# ESP32.net
KiCad netlist of a schematic drawn in Altium Designer
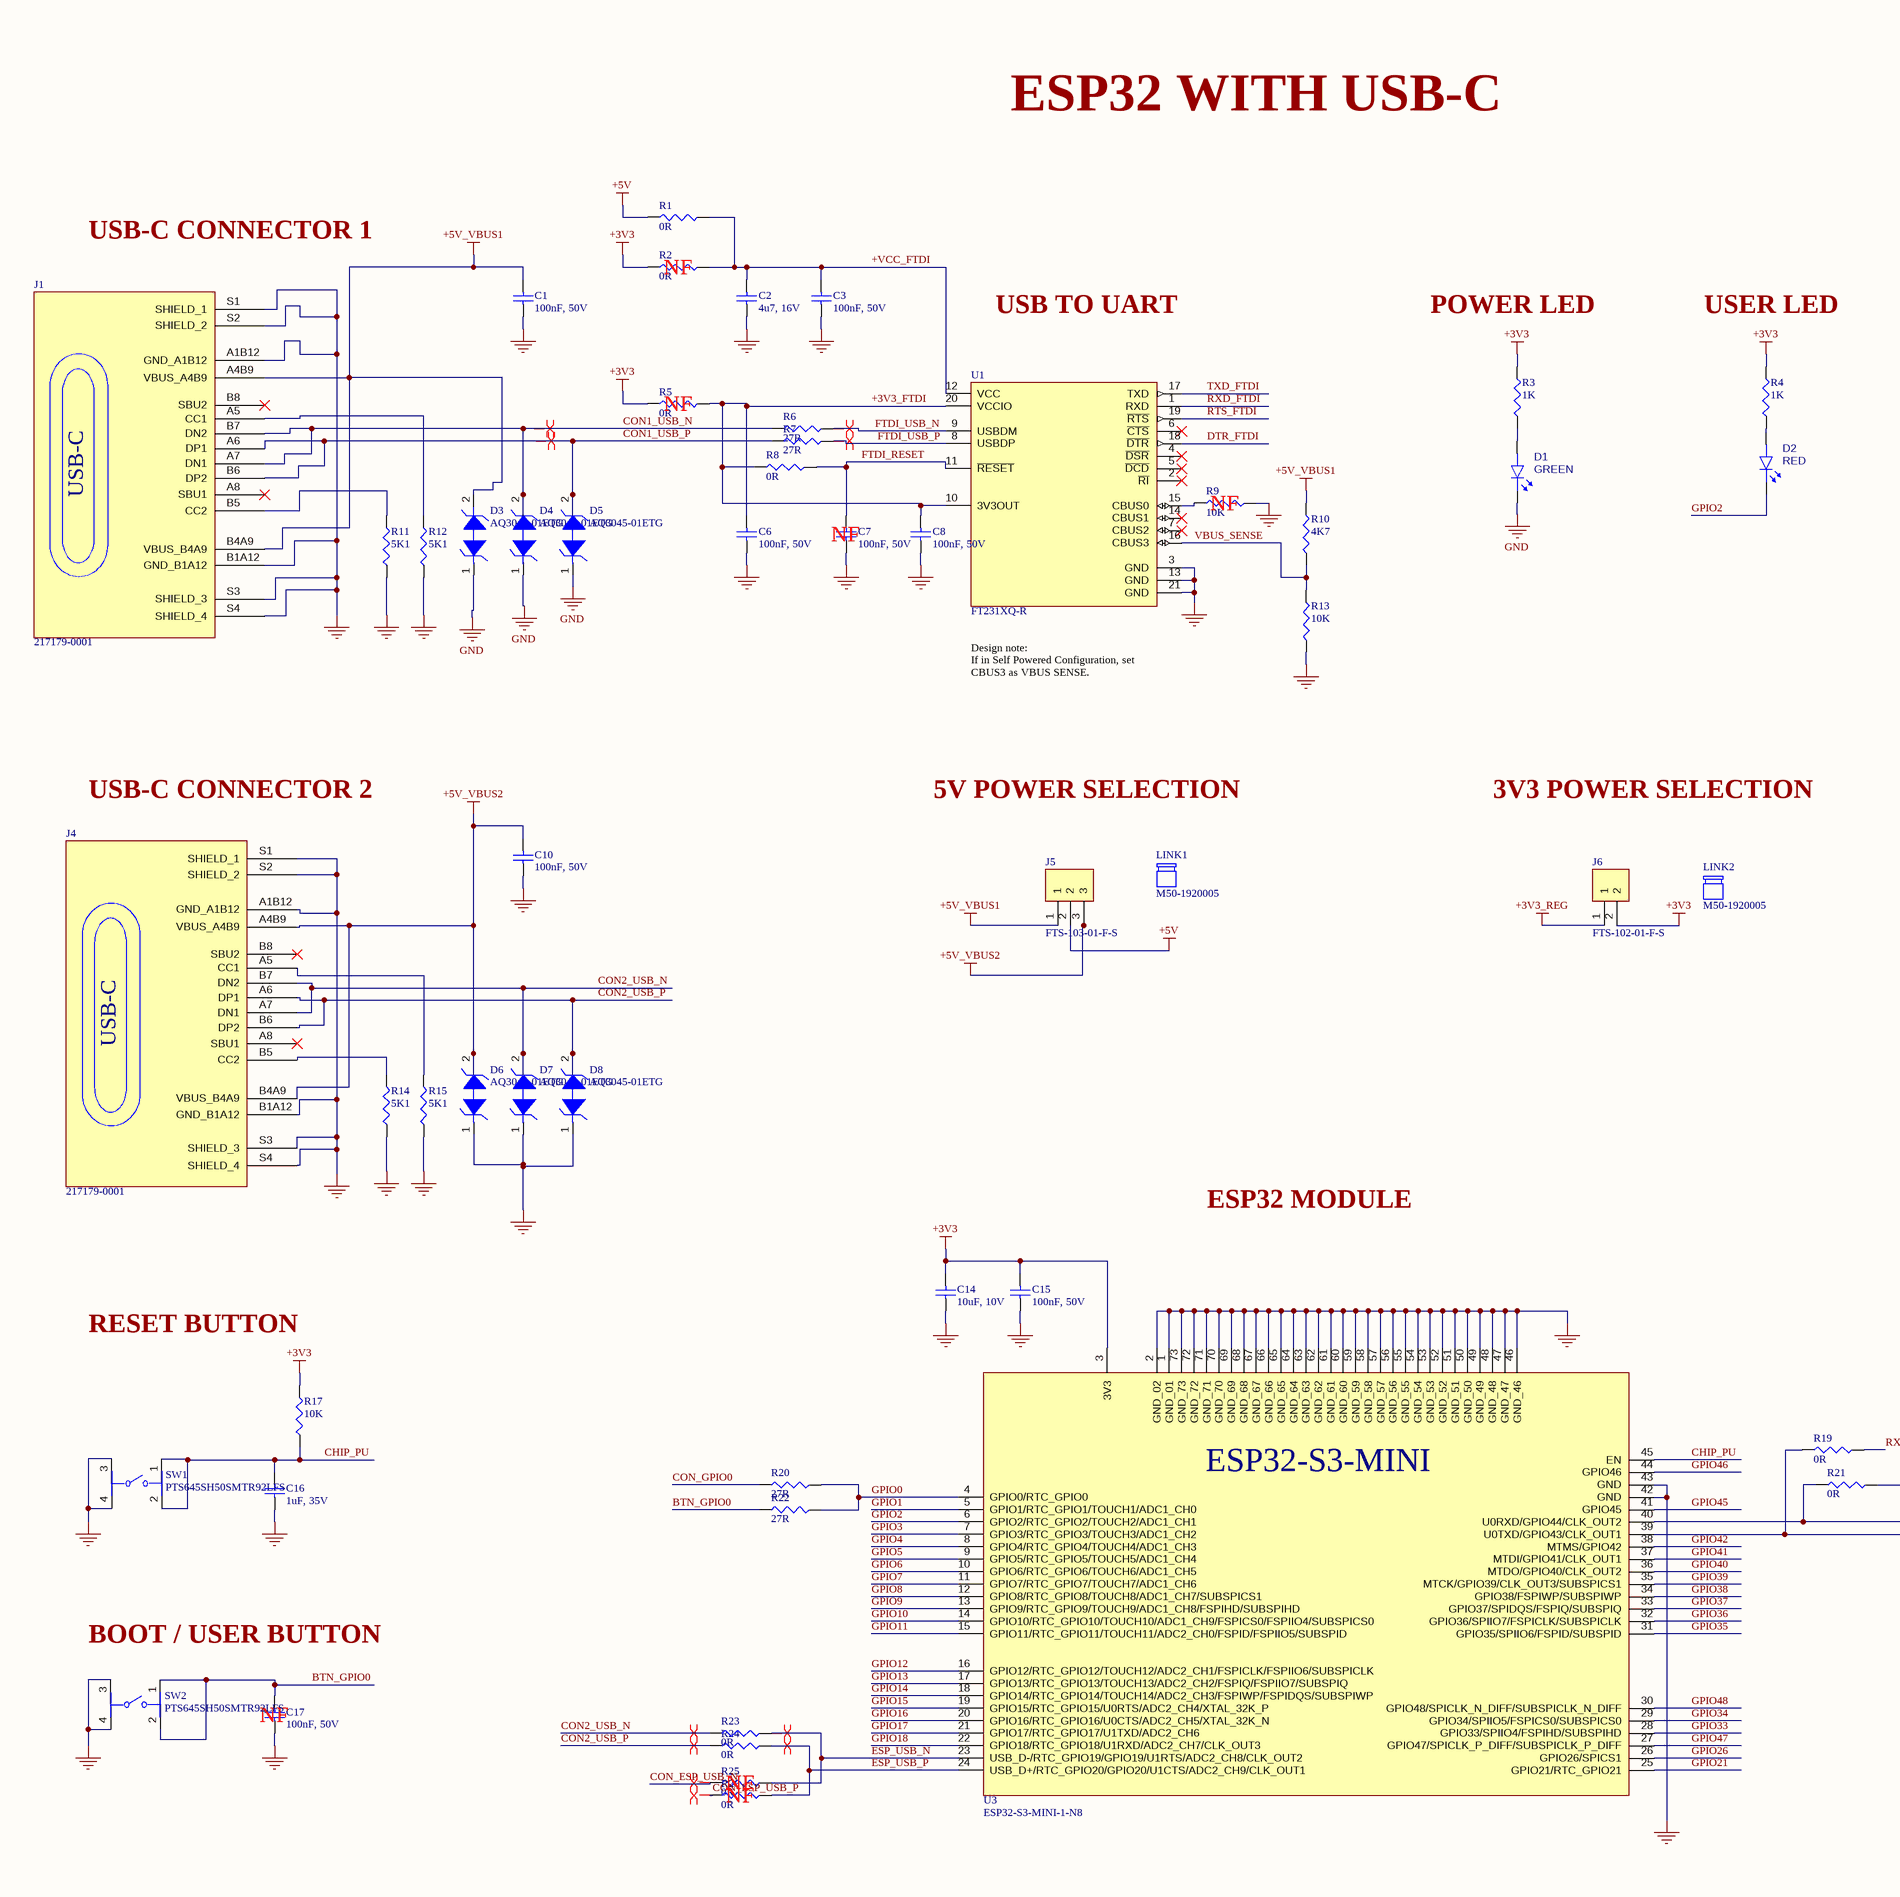
[diagram p0: ESP32.SchDoc, left]
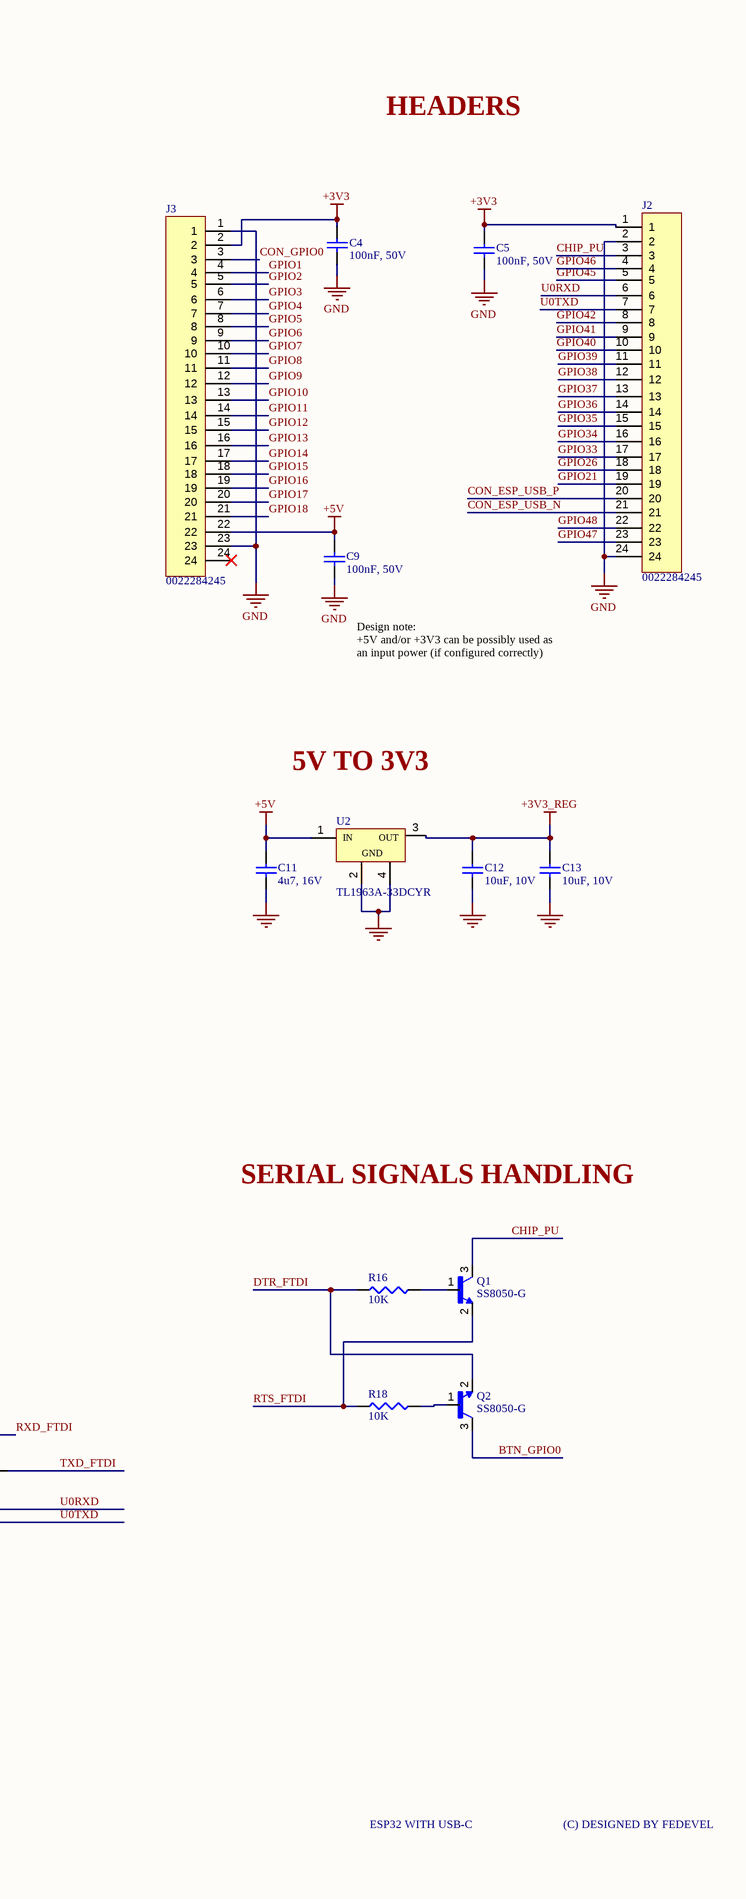
[diagram p1: ESP32.SchDoc, right]

(export (version "E")
  (design (tool "Eeschema 10.0.6"))
  (components
    (comp (ref "C1")
      (value "100nF, 50V")
      (footprint "CAPC1005X55N")
      (description "CAP CER 0.1UF 50V X7R 0402")
      (fields
        (field (name "MANUFACTURER") "Samsung")
        (field (name "MANUFACTURER PART NUMBER") "CL05B104KB54PNC")
      )
      (libsource (lib "ESP32") (part "CL05B104KB54PNC"))
    )
    (comp (ref "C2")
      (value "4u7, 16V")
      (footprint "CAPC1005X55N")
      (description "CAP CER 4.7UF 16V X5R 0402")
      (fields
        (field (name "MANUFACTURER") "Samsung")
        (field (name "MANUFACTURER PART NUMBER") "CL05A475MO5NUNC")
      )
      (libsource (lib "ESP32") (part "CL05A475MO5NUNC"))
    )
    (comp (ref "C3")
      (value "100nF, 50V")
      (footprint "CAPC1005X55N")
      (description "CAP CER 0.1UF 50V X7R 0402")
      (fields
        (field (name "MANUFACTURER") "Samsung")
        (field (name "MANUFACTURER PART NUMBER") "CL05B104KB54PNC")
      )
      (libsource (lib "ESP32") (part "CL05B104KB54PNC"))
    )
    (comp (ref "C4")
      (value "100nF, 50V")
      (footprint "CAPC1005X55N")
      (description "CAP CER 0.1UF 50V X7R 0402")
      (fields
        (field (name "MANUFACTURER") "Samsung")
        (field (name "MANUFACTURER PART NUMBER") "CL05B104KB54PNC")
      )
      (libsource (lib "Schlib") (part "CL05B104KB54PNC"))
    )
    (comp (ref "C5")
      (value "100nF, 50V")
      (footprint "CAPC1005X55N")
      (description "CAP CER 0.1UF 50V X7R 0402")
      (fields
        (field (name "MANUFACTURER") "Samsung")
        (field (name "MANUFACTURER PART NUMBER") "CL05B104KB54PNC")
      )
      (libsource (lib "Schlib") (part "CL05B104KB54PNC"))
    )
    (comp (ref "C6")
      (value "100nF, 50V")
      (footprint "CAPC1005X55N")
      (description "CAP CER 0.1UF 50V X7R 0402")
      (fields
        (field (name "MANUFACTURER") "Samsung")
        (field (name "MANUFACTURER PART NUMBER") "CL05B104KB54PNC")
      )
      (libsource (lib "Schlib") (part "CL05B104KB54PNC"))
    )
    (comp (ref "C7")
      (value "100nF, 50V")
      (footprint "CAPC1005X55N")
      (description "CAP CER 0.1UF 50V X7R 0402")
      (fields
        (field (name "MANUFACTURER") "Samsung")
        (field (name "MANUFACTURER PART NUMBER") "CL05B104KB54PNC")
      )
      (libsource (lib "Schlib") (part "CL05B104KB54PNC"))
    )
    (comp (ref "C8")
      (value "100nF, 50V")
      (footprint "CAPC1005X55N")
      (description "CAP CER 0.1UF 50V X7R 0402")
      (fields
        (field (name "MANUFACTURER") "Samsung")
        (field (name "MANUFACTURER PART NUMBER") "CL05B104KB54PNC")
      )
      (libsource (lib "Schlib") (part "CL05B104KB54PNC"))
    )
    (comp (ref "C9")
      (value "100nF, 50V")
      (footprint "CAPC1005X55N")
      (description "CAP CER 0.1UF 50V X7R 0402")
      (fields
        (field (name "MANUFACTURER") "Samsung")
        (field (name "MANUFACTURER PART NUMBER") "CL05B104KB54PNC")
      )
      (libsource (lib "Schlib") (part "CL05B104KB54PNC"))
    )
    (comp (ref "C10")
      (value "100nF, 50V")
      (footprint "CAPC1005X55N")
      (description "CAP CER 0.1UF 50V X7R 0402")
      (fields
        (field (name "MANUFACTURER") "Samsung")
        (field (name "MANUFACTURER PART NUMBER") "CL05B104KB54PNC")
      )
      (libsource (lib "Schlib") (part "CL05B104KB54PNC"))
    )
    (comp (ref "C11")
      (value "4u7, 16V")
      (footprint "CAPC1005X55N")
      (description "CAP CER 4.7UF 16V X5R 0402")
      (fields
        (field (name "MANUFACTURER") "Samsung")
        (field (name "MANUFACTURER PART NUMBER") "CL05A475MO5NUNC")
      )
      (libsource (lib "Schlib") (part "CL05A475MO5NUNC"))
    )
    (comp (ref "C12")
      (value "10uF, 10V")
      (footprint "CAPC1005X55N")
      (description "CAP CER 10UF 10V X5R 0402")
      (fields
        (field (name "MANUFACTURER") "Samsung")
        (field (name "MANUFACTURER PART NUMBER") "CL05A106MP8NUB8")
      )
      (libsource (lib "ESP32") (part "CL05A106MP8NUB8"))
    )
    (comp (ref "C13")
      (value "10uF, 10V")
      (footprint "CAPC1005X55N")
      (description "CAP CER 10UF 10V X5R 0402")
      (fields
        (field (name "MANUFACTURER") "Samsung")
        (field (name "MANUFACTURER PART NUMBER") "CL05A106MP8NUB8")
      )
      (libsource (lib "Schlib") (part "CL05A106MP8NUB8"))
    )
    (comp (ref "C14")
      (value "10uF, 10V")
      (footprint "CAPC1005X55N")
      (description "CAP CER 10UF 10V X5R 0402")
      (fields
        (field (name "MANUFACTURER") "Samsung")
        (field (name "MANUFACTURER PART NUMBER") "CL05A106MP8NUB8")
      )
      (libsource (lib "ESP32") (part "CL05A106MP8NUB8"))
    )
    (comp (ref "C15")
      (value "100nF, 50V")
      (footprint "CAPC1005X55N")
      (description "CAP CER 0.1UF 50V X7R 0402")
      (fields
        (field (name "MANUFACTURER") "Samsung")
        (field (name "MANUFACTURER PART NUMBER") "CL05B104KB54PNC")
      )
      (libsource (lib "ESP32") (part "CL05B104KB54PNC"))
    )
    (comp (ref "C16")
      (value "1uF, 35V")
      (footprint "CAPC1005X55N")
      (description "CAP CER 1UF 35V X5R 0402")
      (fields
        (field (name "MANUFACTURER") "Samsung")
        (field (name "MANUFACTURER PART NUMBER") "CL05A105KL5NRNC")
      )
      (libsource (lib "Schlib") (part "CL05A105KL5NRNC"))
    )
    (comp (ref "C17")
      (value "100nF, 50V")
      (footprint "CAPC1005X55N")
      (description "CAP CER 0.1UF 50V X7R 0402")
      (fields
        (field (name "MANUFACTURER") "Samsung")
        (field (name "MANUFACTURER PART NUMBER") "CL05B104KB54PNC")
      )
      (libsource (lib "Schlib") (part "CL05B104KB54PNC"))
    )
    (comp (ref "D1")
      (value "GREEN")
      (footprint "QTB-QBLP595_V")
      (description "Chip LED 0402, Green, 0.02 A, 3.1 to 3.7 V, -40 to 80 degC, 2-Pin SMD, RoHS, Tape and Reel")
      (libsource (lib "KARTHICK RAJ R") (part "LED-KA-2"))
    )
    (comp (ref "D2")
      (value "RED")
      (footprint "QTB-QBLP595_V")
      (description "Chip LED 0402, Red, 0.02 A, 2.0 to 2.5 V, -40 to 80 degC, 2-Pin SMD, RoHS, Tape and Reel")
      (libsource (lib "KARTHICK RAJ R") (part "LED-KA-2"))
    )
    (comp (ref "D3")
      (value "AQ3045-01ETG")
      (footprint "AQ3045-01ETG")
      (description "Bi 30Kv 5V 0.35Pf Automotve Tvs Sod882/ T&r Rohs Compliant: Yes ¦Littelfuse AQ3045-01ETG")
      (fields (field (name "MANUFACTURER") "Littelfuse"))
      (libsource (lib "ESP32") (part "AQ3045-01ETG"))
    )
    (comp (ref "D4")
      (value "AQ3045-01ETG")
      (footprint "AQ3045-01ETG")
      (description "Bi 30Kv 5V 0.35Pf Automotve Tvs Sod882/ T&r Rohs Compliant: Yes ¦Littelfuse AQ3045-01ETG")
      (fields (field (name "MANUFACTURER") "Littelfuse"))
      (libsource (lib "ESP32") (part "AQ3045-01ETG"))
    )
    (comp (ref "D5")
      (value "AQ3045-01ETG")
      (footprint "AQ3045-01ETG")
      (description "Bi 30Kv 5V 0.35Pf Automotve Tvs Sod882/ T&r Rohs Compliant: Yes ¦Littelfuse AQ3045-01ETG")
      (fields (field (name "MANUFACTURER") "Littelfuse"))
      (libsource (lib "ESP32") (part "AQ3045-01ETG"))
    )
    (comp (ref "D6")
      (value "AQ3045-01ETG")
      (footprint "AQ3045-01ETG")
      (description "Bi 30Kv 5V 0.35Pf Automotve Tvs Sod882/ T&r Rohs Compliant: Yes ¦Littelfuse AQ3045-01ETG")
      (fields (field (name "MANUFACTURER") "Littelfuse"))
      (libsource (lib "ESP32") (part "AQ3045-01ETG"))
    )
    (comp (ref "D7")
      (value "AQ3045-01ETG")
      (footprint "AQ3045-01ETG")
      (description "Bi 30Kv 5V 0.35Pf Automotve Tvs Sod882/ T&r Rohs Compliant: Yes ¦Littelfuse AQ3045-01ETG")
      (fields (field (name "MANUFACTURER") "Littelfuse"))
      (libsource (lib "ESP32") (part "AQ3045-01ETG"))
    )
    (comp (ref "D8")
      (value "AQ3045-01ETG")
      (footprint "AQ3045-01ETG")
      (description "Bi 30Kv 5V 0.35Pf Automotve Tvs Sod882/ T&r Rohs Compliant: Yes ¦Littelfuse AQ3045-01ETG")
      (fields (field (name "MANUFACTURER") "Littelfuse"))
      (libsource (lib "ESP32") (part "AQ3045-01ETG"))
    )
    (comp (ref "J1")
      (value "217179-0001")
      (footprint "2171790001")
      (description "USB Connector, USB Type C, USB 2.0, Receptacle, 16 Ways, Surface Mount, Through Hole Mount")
      (fields (field (name "MANUFACTURER") "Molex"))
      (libsource (lib "ESP32") (part "217179-0001"))
    )
    (comp (ref "J2")
      (value "0022284245")
      (footprint "0022284245")
      (description "Conn Unshrouded Header HDR 24 POS 2.54mm Solder ST Thru-Hole KK® Bag")
      (fields (field (name "MANUFACTURER") "Molex") (field (name "MANUFACTURER PART NUMBER") "22-28-4245"))
      (libsource (lib "ESP32") (part "0022284245"))
    )
    (comp (ref "J3")
      (value "0022284245")
      (footprint "0022284245")
      (description "Conn Unshrouded Header HDR 24 POS 2.54mm Solder ST Thru-Hole KK® Bag")
      (fields (field (name "MANUFACTURER") "Molex") (field (name "MANUFACTURER PART NUMBER") "22-28-4245"))
      (libsource (lib "") (part "0022284245_1"))
    )
    (comp (ref "J4")
      (value "217179-0001")
      (footprint "2171790001")
      (description "USB Connector, USB Type C, USB 2.0, Receptacle, 16 Ways, Surface Mount, Through Hole Mount")
      (fields (field (name "MANUFACTURER") "Molex"))
      (libsource (lib "ESP32") (part "217179-0001"))
    )
    (comp (ref "J5")
      (value "FTS-103-01-F-S")
      (footprint "FTS-103-01-X-S")
      (description "Pin Header, Wire-to-Board, 1.27 mm, 1 Rows, 3 Contacts, Through Hole, FTS")
      (fields (field (name "MANUFACTURER") "Samtec") (field (name "LCSC PART NUMBER") "C3333578"))
      (libsource (lib "ESP32") (part "FTS-103-01-F-S"))
    )
    (comp (ref "J6")
      (value "FTS-102-01-F-S")
      (footprint "FTS-102-01-X-S")
      (description "Pin Header, Board-to-Board, 1.27 mm, 1 Rows, 2 Contacts, Through Hole Straight, FTS Series")
      (fields (field (name "MANUFACTURER") "Samtec"))
      (libsource (lib "ESP32") (part "FTS-102-01-F-S"))
    )
    (comp (ref "LINK1")
      (value "M50-1920005")
      (description "CONN SHUNT 1.27MM RED")
      (fields (field (name "MANUFACTURER") "Harwin") (field (name "LCSC PART NUMBER") "C6985646"))
      (libsource (lib "ESP32") (part "M50-1920005"))
    )
    (comp (ref "LINK2")
      (value "M50-1920005")
      (description "CONN SHUNT 1.27MM RED")
      (fields (field (name "MANUFACTURER") "Harwin") (field (name "LCSC PART NUMBER") "C6985646"))
      (libsource (lib "ESP32") (part "M50-1920005"))
    )
    (comp (ref "Q1")
      (value "SS8050-G")
      (footprint "SS8050-G")
      (description "Bipolar (BJT) Transistor NPN 25 V 1.5 A 100MHz 300 mW Surface Mount SOT-23-3")
      (fields (field (name "DIGI-KEY_PART_NUMBER") "641-1790-2-ND") (field (name "MP") "SS8050G"))
      (libsource (lib "ESP32") (part "SS8050-G"))
    )
    (comp (ref "Q2")
      (value "SS8050-G")
      (footprint "SS8050-G")
      (description "Bipolar (BJT) Transistor NPN 25 V 1.5 A 100MHz 300 mW Surface Mount SOT-23-3")
      (fields (field (name "DIGI-KEY_PART_NUMBER") "641-1790-2-ND") (field (name "MP") "SS8050G"))
      (libsource (lib "") (part "SS8050-G_1"))
    )
    (comp (ref "R1")
      (value "0R")
      (footprint "RES-2")
      (description "RES 0 OHM JUMPER 1/16W 0402")
      (fields
        (field (name "MANUFACTURER") "Yageo")
        (field (name "MANUFACTURER PART NUMBER") "RC0402JR-070RL")
      )
      (libsource (lib "Schlib") (part "RC0402JR-070RL"))
    )
    (comp (ref "R2")
      (value "0R")
      (footprint "RES-2")
      (description "RES 0 OHM JUMPER 1/16W 0402")
      (fields
        (field (name "MANUFACTURER") "Yageo")
        (field (name "MANUFACTURER PART NUMBER") "RC0402JR-070RL")
      )
      (libsource (lib "Schlib") (part "RC0402JR-070RL"))
    )
    (comp (ref "R3")
      (value "1K")
      (footprint "RES-2")
      (description "RES 1K OHM 1% 1/16W 0402")
      (fields
        (field (name "MANUFACTURER") "Yageo")
        (field (name "MANUFACTURER PART NUMBER") "RC0402FR-071KL")
      )
      (libsource (lib "Schlib") (part "RC0402FR-071KL"))
    )
    (comp (ref "R4")
      (value "1K")
      (footprint "RES-2")
      (description "RES 1K OHM 1% 1/16W 0402")
      (fields
        (field (name "MANUFACTURER") "Yageo")
        (field (name "MANUFACTURER PART NUMBER") "RC0402FR-071KL")
      )
      (libsource (lib "Schlib") (part "RC0402FR-071KL"))
    )
    (comp (ref "R5")
      (value "0R")
      (footprint "RES-2")
      (description "RES 0 OHM JUMPER 1/16W 0402")
      (fields
        (field (name "MANUFACTURER") "Yageo")
        (field (name "MANUFACTURER PART NUMBER") "RC0402JR-070RL")
      )
      (libsource (lib "Schlib") (part "RC0402JR-070RL"))
    )
    (comp (ref "R6")
      (value "27R")
      (footprint "RES-2")
      (description "RES 27 OHM 1% 1/16W 0402")
      (fields
        (field (name "MANUFACTURER") "Yageo")
        (field (name "MANUFACTURER PART NUMBER") "RC0402FR-0727RL")
      )
      (libsource (lib "Schlib") (part "RC0402FR-0727RL"))
    )
    (comp (ref "R7")
      (value "27R")
      (footprint "RES-2")
      (description "RES 27 OHM 1% 1/16W 0402")
      (fields
        (field (name "MANUFACTURER") "Yageo")
        (field (name "MANUFACTURER PART NUMBER") "RC0402FR-0727RL")
      )
      (libsource (lib "Schlib") (part "RC0402FR-0727RL"))
    )
    (comp (ref "R8")
      (value "0R")
      (footprint "RES-2")
      (description "RES 0 OHM JUMPER 1/16W 0402")
      (fields
        (field (name "MANUFACTURER") "Yageo")
        (field (name "MANUFACTURER PART NUMBER") "RC0402JR-070RL")
      )
      (libsource (lib "Schlib") (part "RC0402JR-070RL"))
    )
    (comp (ref "R9")
      (value "10K")
      (footprint "RES-2")
      (description "RES SMD 10K OHM 1% 1/16W 0402")
      (fields
        (field (name "MANUFACTURER") "Yageo")
        (field (name "MANUFACTURER PART NUMBER") "AC0402FR-0710KL")
      )
      (libsource (lib "Schlib") (part "AC0402FR-0710KL"))
    )
    (comp (ref "R10")
      (value "4K7")
      (footprint "RES-2")
      (description "RES 4.7K OHM 1% 1/16W 0402")
      (fields
        (field (name "MANUFACTURER") "Yageo")
        (field (name "MANUFACTURER PART NUMBER") "RC0402FR-074K7L")
      )
      (libsource (lib "Schlib") (part "RC0402FR-074K7L"))
    )
    (comp (ref "R11")
      (value "5K1")
      (footprint "RES-2")
      (description "RES SMD 5.1K OHM 1% 1/16W 0402")
      (fields
        (field (name "MANUFACTURER") "Yageo")
        (field (name "MANUFACTURER PART NUMBER") "AC0402FR-075K1L")
      )
      (libsource (lib "Schlib") (part "AC0402FR-075K1L"))
    )
    (comp (ref "R12")
      (value "5K1")
      (footprint "RES-2")
      (description "RES SMD 5.1K OHM 1% 1/16W 0402")
      (fields
        (field (name "MANUFACTURER") "Yageo")
        (field (name "MANUFACTURER PART NUMBER") "AC0402FR-075K1L")
      )
      (libsource (lib "Schlib") (part "AC0402FR-075K1L"))
    )
    (comp (ref "R13")
      (value "10K")
      (footprint "RES-2")
      (description "RES SMD 10K OHM 1% 1/16W 0402")
      (fields
        (field (name "MANUFACTURER") "Yageo")
        (field (name "MANUFACTURER PART NUMBER") "AC0402FR-0710KL")
      )
      (libsource (lib "Schlib") (part "AC0402FR-0710KL"))
    )
    (comp (ref "R14")
      (value "5K1")
      (footprint "RES-2")
      (description "RES SMD 5.1K OHM 1% 1/16W 0402")
      (fields
        (field (name "MANUFACTURER") "Yageo")
        (field (name "MANUFACTURER PART NUMBER") "AC0402FR-075K1L")
      )
      (libsource (lib "Schlib") (part "AC0402FR-075K1L"))
    )
    (comp (ref "R15")
      (value "5K1")
      (footprint "RES-2")
      (description "RES SMD 5.1K OHM 1% 1/16W 0402")
      (fields
        (field (name "MANUFACTURER") "Yageo")
        (field (name "MANUFACTURER PART NUMBER") "AC0402FR-075K1L")
      )
      (libsource (lib "Schlib") (part "AC0402FR-075K1L"))
    )
    (comp (ref "R16")
      (value "10K")
      (footprint "RES-2")
      (description "RES SMD 10K OHM 1% 1/16W 0402")
      (fields
        (field (name "MANUFACTURER") "Yageo")
        (field (name "MANUFACTURER PART NUMBER") "AC0402FR-0710KL")
      )
      (libsource (lib "Schlib") (part "AC0402FR-0710KL"))
    )
    (comp (ref "R17")
      (value "10K")
      (footprint "RES-2")
      (description "RES SMD 10K OHM 1% 1/16W 0402")
      (fields
        (field (name "MANUFACTURER") "Yageo")
        (field (name "MANUFACTURER PART NUMBER") "AC0402FR-0710KL")
      )
      (libsource (lib "Schlib") (part "AC0402FR-0710KL"))
    )
    (comp (ref "R18")
      (value "10K")
      (footprint "RES-2")
      (description "RES SMD 10K OHM 1% 1/16W 0402")
      (fields
        (field (name "MANUFACTURER") "Yageo")
        (field (name "MANUFACTURER PART NUMBER") "AC0402FR-0710KL")
      )
      (libsource (lib "Schlib") (part "AC0402FR-0710KL"))
    )
    (comp (ref "R19")
      (value "0R")
      (footprint "RES-2")
      (description "RES 0 OHM JUMPER 1/16W 0402")
      (fields
        (field (name "MANUFACTURER") "Yageo")
        (field (name "MANUFACTURER PART NUMBER") "RC0402JR-070RL")
      )
      (libsource (lib "Schlib") (part "RC0402JR-070RL"))
    )
    (comp (ref "R20")
      (value "27R")
      (footprint "RES-2")
      (description "RES 27 OHM 1% 1/16W 0402")
      (fields
        (field (name "MANUFACTURER") "Yageo")
        (field (name "MANUFACTURER PART NUMBER") "RC0402FR-0727RL")
      )
      (libsource (lib "Schlib") (part "RC0402FR-0727RL"))
    )
    (comp (ref "R21")
      (value "0R")
      (footprint "RES-2")
      (description "RES 0 OHM JUMPER 1/16W 0402")
      (fields
        (field (name "MANUFACTURER") "Yageo")
        (field (name "MANUFACTURER PART NUMBER") "RC0402JR-070RL")
      )
      (libsource (lib "Schlib") (part "RC0402JR-070RL"))
    )
    (comp (ref "R22")
      (value "27R")
      (footprint "RES-2")
      (description "RES 27 OHM 1% 1/16W 0402")
      (fields
        (field (name "MANUFACTURER") "Yageo")
        (field (name "MANUFACTURER PART NUMBER") "RC0402FR-0727RL")
      )
      (libsource (lib "Schlib") (part "RC0402FR-0727RL"))
    )
    (comp (ref "R23")
      (value "0R")
      (footprint "RES-2")
      (description "RES 0 OHM JUMPER 1/16W 0402")
      (fields
        (field (name "MANUFACTURER") "Yageo")
        (field (name "MANUFACTURER PART NUMBER") "RC0402JR-070RL")
      )
      (libsource (lib "Schlib") (part "RC0402JR-070RL"))
    )
    (comp (ref "R24")
      (value "0R")
      (footprint "RES-2")
      (description "RES 0 OHM JUMPER 1/16W 0402")
      (fields
        (field (name "MANUFACTURER") "Yageo")
        (field (name "MANUFACTURER PART NUMBER") "RC0402JR-070RL")
      )
      (libsource (lib "Schlib") (part "RC0402JR-070RL"))
    )
    (comp (ref "R25")
      (value "0R")
      (footprint "RES-2")
      (description "RES 0 OHM JUMPER 1/16W 0402")
      (fields
        (field (name "MANUFACTURER") "Yageo")
        (field (name "MANUFACTURER PART NUMBER") "RC0402JR-070RL")
      )
      (libsource (lib "Schlib") (part "RC0402JR-070RL"))
    )
    (comp (ref "R26")
      (value "0R")
      (footprint "RES-2")
      (description "RES 0 OHM JUMPER 1/16W 0402")
      (fields
        (field (name "MANUFACTURER") "Yageo")
        (field (name "MANUFACTURER PART NUMBER") "RC0402JR-070RL")
      )
      (libsource (lib "Schlib") (part "RC0402JR-070RL"))
    )
    (comp (ref "SW1")
      (value "PTS645SH50SMTR92LFS")
      (footprint "switch")
      (description "SWITCH TACTILE SPST-NO 0.05A 12V")
      (libsource (lib "ESP32") (part "CMP-10040-000028-1"))
    )
    (comp (ref "SW2")
      (value "PTS645SH50SMTR92LFS")
      (footprint "switch")
      (description "SWITCH TACTILE SPST-NO 0.05A 12V")
      (libsource (lib "ESP32") (part "CMP-10040-000028-1"))
    )
    (comp (ref "U1")
      (value "FT231XQ-R")
      (footprint "FT231XQ-R")
      (description "IC USB SERIAL FULL UART 20QFN")
      (libsource (lib "ESP32") (part "FT231XQ-R"))
    )
    (comp (ref "U2")
      (value "TL1963A-33DCYR")
      (footprint "TL1963A-33DCYR")
      (libsource (lib "ESP32") (part "TL1963A-33DCYR"))
    )
    (comp (ref "U3")
      (value "ESP32-S3-MINI-1-N8")
      (footprint "ESP32-S3-MINI-1-N8")
      (description "SMD Module, ESP32-S3FN8, 8 mb Sp")
      (fields (field (name "MANUFACTURER") "Espressif Systems") (field (name "LCSC PART NUMBER") "C2913206"))
      (libsource (lib "Schlib") (part "ESP32-S3-MINI-1-N8"))
    )
  )
  (nets
    (net (code "1") (name "+3V3") (class "Default")
      (node (ref "C14") (pin "2") (pinfunction "2_2") (pintype "passive"))
      (node (ref "C15") (pin "2") (pinfunction "2_2") (pintype "passive"))
      (node (ref "C4") (pin "2") (pinfunction "2_2") (pintype "passive"))
      (node (ref "C5") (pin "2") (pinfunction "2_2") (pintype "passive"))
      (node (ref "J2") (pin "1") (pinfunction "1_1") (pintype "passive"))
      (node (ref "J3") (pin "2") (pinfunction "2_2") (pintype "passive"))
      (node (ref "J6") (pin "2") (pinfunction "2_2") (pintype "passive"))
      (node (ref "R17") (pin "2") (pinfunction "2_2") (pintype "passive"))
      (node (ref "R2") (pin "1") (pinfunction "1_1") (pintype "passive"))
      (node (ref "R3") (pin "2") (pinfunction "2_2") (pintype "passive"))
      (node (ref "R4") (pin "2") (pinfunction "2_2") (pintype "passive"))
      (node (ref "R5") (pin "1") (pinfunction "1_1") (pintype "passive"))
      (node (ref "U3") (pin "3") (pinfunction "3V3_3") (pintype "passive"))
    )
    (net (code "2") (name "+3V3_REG") (class "Default")
      (node (ref "C12") (pin "2") (pinfunction "2_2") (pintype "passive"))
      (node (ref "C13") (pin "2") (pinfunction "2_2") (pintype "passive"))
      (node (ref "J6") (pin "1") (pinfunction "1_1") (pintype "passive"))
      (node (ref "U2") (pin "3") (pinfunction "44_3") (pintype "passive"))
    )
    (net (code "3") (name "+5V") (class "Default")
      (node (ref "C11") (pin "2") (pinfunction "2_2") (pintype "passive"))
      (node (ref "C9") (pin "2") (pinfunction "2_2") (pintype "passive"))
      (node (ref "J3") (pin "22") (pinfunction "22_22") (pintype "passive"))
      (node (ref "J5") (pin "2") (pinfunction "2_2") (pintype "passive"))
      (node (ref "R1") (pin "1") (pinfunction "1_1") (pintype "passive"))
      (node (ref "U2") (pin "1") (pinfunction "42_1") (pintype "passive"))
    )
    (net (code "4") (name "+5V_VBUS1") (class "Default")
      (node (ref "C1") (pin "2") (pinfunction "2_2") (pintype "passive"))
      (node (ref "D3") (pin "2") (pinfunction "1_2") (pintype "passive"))
      (node (ref "J1") (pin "A4B9") (pinfunction "VBUS_A4B9_A4B9") (pintype "passive"))
      (node (ref "J1") (pin "B4A9") (pinfunction "VBUS_B4A9_B4A9") (pintype "passive"))
      (node (ref "J5") (pin "1") (pinfunction "1_1") (pintype "passive"))
      (node (ref "R10") (pin "2") (pinfunction "2_2") (pintype "passive"))
    )
    (net (code "5") (name "+5V_VBUS2") (class "Default")
      (node (ref "C10") (pin "2") (pinfunction "2_2") (pintype "passive"))
      (node (ref "D6") (pin "2") (pinfunction "1_2") (pintype "passive"))
      (node (ref "J4") (pin "A4B9") (pinfunction "VBUS_A4B9_A4B9") (pintype "passive"))
      (node (ref "J4") (pin "B4A9") (pinfunction "VBUS_B4A9_B4A9") (pintype "passive"))
      (node (ref "J5") (pin "3") (pinfunction "3_3") (pintype "passive"))
    )
    (net (code "6") (name "/+3V3_FTDI") (class "Default")
      (node (ref "C6") (pin "2") (pinfunction "2_2") (pintype "passive"))
      (node (ref "C8") (pin "2") (pinfunction "2_2") (pintype "passive"))
      (node (ref "R5") (pin "2") (pinfunction "2_2") (pintype "passive"))
      (node (ref "R8") (pin "1") (pinfunction "1_1") (pintype "passive"))
      (node (ref "U1") (pin "10") (pinfunction "3V3OUT_10") (pintype "power_in"))
      (node (ref "U1") (pin "20") (pinfunction "VCCIO_20") (pintype "power_in"))
    )
    (net (code "7") (name "/+VCC_FTDI") (class "Default")
      (node (ref "C2") (pin "2") (pinfunction "2_2") (pintype "passive"))
      (node (ref "C3") (pin "2") (pinfunction "2_2") (pintype "passive"))
      (node (ref "R1") (pin "2") (pinfunction "2_2") (pintype "passive"))
      (node (ref "R2") (pin "2") (pinfunction "2_2") (pintype "passive"))
      (node (ref "U1") (pin "12") (pinfunction "VCC_12") (pintype "power_in"))
    )
    (net (code "8") (name "/BTN_GPIO0") (class "Default")
      (node (ref "C17") (pin "2") (pinfunction "2_2") (pintype "passive"))
      (node (ref "Q2") (pin "3") (pinfunction "C_3") (pintype "passive"))
      (node (ref "R22") (pin "1") (pinfunction "1_1") (pintype "passive"))
      (node (ref "SW2") (pin "1") (pinfunction "1_1") (pintype "passive"))
      (node (ref "SW2") (pin "2") (pinfunction "2_2") (pintype "passive"))
    )
    (net (code "9") (name "/CHIP_PU") (class "Default")
      (node (ref "C16") (pin "2") (pinfunction "2_2") (pintype "passive"))
      (node (ref "J2") (pin "3") (pinfunction "3_3") (pintype "passive"))
      (node (ref "Q1") (pin "3") (pinfunction "C_3") (pintype "passive"))
      (node (ref "R17") (pin "1") (pinfunction "1_1") (pintype "passive"))
      (node (ref "SW1") (pin "1") (pinfunction "1_1") (pintype "passive"))
      (node (ref "SW1") (pin "2") (pinfunction "2_2") (pintype "passive"))
      (node (ref "U3") (pin "45") (pinfunction "EN_45") (pintype "passive"))
    )
    (net (code "10") (name "/CON1_USB_N") (class "Default")
      (node (ref "D4") (pin "2") (pinfunction "1_2") (pintype "passive"))
      (node (ref "J1") (pin "A7") (pinfunction "DN1_A7") (pintype "passive"))
      (node (ref "J1") (pin "B7") (pinfunction "DN2_B7") (pintype "passive"))
      (node (ref "R6") (pin "1") (pinfunction "1_1") (pintype "passive"))
    )
    (net (code "11") (name "/CON1_USB_P") (class "Default")
      (node (ref "D5") (pin "2") (pinfunction "1_2") (pintype "passive"))
      (node (ref "J1") (pin "A6") (pinfunction "DP1_A6") (pintype "passive"))
      (node (ref "J1") (pin "B6") (pinfunction "DP2_B6") (pintype "passive"))
      (node (ref "R7") (pin "1") (pinfunction "1_1") (pintype "passive"))
    )
    (net (code "12") (name "/CON2_USB_N") (class "Default")
      (node (ref "D7") (pin "2") (pinfunction "1_2") (pintype "passive"))
      (node (ref "J4") (pin "A7") (pinfunction "DN1_A7") (pintype "passive"))
      (node (ref "J4") (pin "B7") (pinfunction "DN2_B7") (pintype "passive"))
      (node (ref "R23") (pin "1") (pinfunction "1_1") (pintype "passive"))
    )
    (net (code "13") (name "/CON2_USB_P") (class "Default")
      (node (ref "D8") (pin "2") (pinfunction "1_2") (pintype "passive"))
      (node (ref "J4") (pin "A6") (pinfunction "DP1_A6") (pintype "passive"))
      (node (ref "J4") (pin "B6") (pinfunction "DP2_B6") (pintype "passive"))
      (node (ref "R24") (pin "1") (pinfunction "1_1") (pintype "passive"))
    )
    (net (code "14") (name "/CON_ESP_USB_N") (class "Default")
      (node (ref "J2") (pin "21") (pinfunction "21_21") (pintype "passive"))
      (node (ref "R25") (pin "1") (pinfunction "1_1") (pintype "passive"))
    )
    (net (code "15") (name "/CON_ESP_USB_P") (class "Default")
      (node (ref "J2") (pin "20") (pinfunction "20_20") (pintype "passive"))
      (node (ref "R26") (pin "1") (pinfunction "1_1") (pintype "passive"))
    )
    (net (code "16") (name "/CON_GPIO0") (class "Default")
      (node (ref "J3") (pin "3") (pinfunction "3_3") (pintype "passive"))
      (node (ref "R20") (pin "1") (pinfunction "1_1") (pintype "passive"))
    )
    (net (code "17") (name "/DTR_FTDI") (class "Default")
      (node (ref "Q2") (pin "2") (pinfunction "E_2") (pintype "passive"))
      (node (ref "R16") (pin "1") (pinfunction "1_1") (pintype "passive"))
      (node (ref "U1") (pin "18") (pinfunction "~{DTR}_18") (pintype "output"))
    )
    (net (code "18") (name "/ESP_USB_N") (class "Default")
      (node (ref "R23") (pin "2") (pinfunction "2_2") (pintype "passive"))
      (node (ref "R25") (pin "2") (pinfunction "2_2") (pintype "passive"))
      (node (ref "U3") (pin "23") (pinfunction "USB_D-/RTC_GPIO19/GPIO19/U1RTS/ADC2_CH8/CLK_OUT2_23") (pintype "passive"))
    )
    (net (code "19") (name "/ESP_USB_P") (class "Default")
      (node (ref "R24") (pin "2") (pinfunction "2_2") (pintype "passive"))
      (node (ref "R26") (pin "2") (pinfunction "2_2") (pintype "passive"))
      (node (ref "U3") (pin "24") (pinfunction "USB_D+/RTC_GPIO20/GPIO20/U1CTS/ADC2_CH9/CLK_OUT1_24") (pintype "passive"))
    )
    (net (code "20") (name "/FTDI_RESET") (class "Default")
      (node (ref "C7") (pin "2") (pinfunction "2_2") (pintype "passive"))
      (node (ref "R8") (pin "2") (pinfunction "2_2") (pintype "passive"))
      (node (ref "U1") (pin "11") (pinfunction "~{RESET}_11") (pintype "passive"))
    )
    (net (code "21") (name "/FTDI_USB_N") (class "Default")
      (node (ref "R6") (pin "2") (pinfunction "2_2") (pintype "passive"))
      (node (ref "U1") (pin "9") (pinfunction "USBDM_9") (pintype "passive"))
    )
    (net (code "22") (name "/FTDI_USB_P") (class "Default")
      (node (ref "R7") (pin "2") (pinfunction "2_2") (pintype "passive"))
      (node (ref "U1") (pin "8") (pinfunction "USBDP_8") (pintype "passive"))
    )
    (net (code "23") (name "/GPIO0") (class "Default")
      (node (ref "R20") (pin "2") (pinfunction "2_2") (pintype "passive"))
      (node (ref "R22") (pin "2") (pinfunction "2_2") (pintype "passive"))
      (node (ref "U3") (pin "4") (pinfunction "GPIO0/RTC_GPIO0_4") (pintype "passive"))
    )
    (net (code "24") (name "/GPIO1") (class "Default")
      (node (ref "J3") (pin "4") (pinfunction "4_4") (pintype "passive"))
      (node (ref "U3") (pin "5") (pinfunction "GPIO1/RTC_GPIO1/TOUCH1/ADC1_CH0_5") (pintype "passive"))
    )
    (net (code "25") (name "/GPIO2") (class "Default")
      (node (ref "D2") (pin "1") (pinfunction "K_1") (pintype "passive"))
      (node (ref "J3") (pin "5") (pinfunction "5_5") (pintype "passive"))
      (node (ref "U3") (pin "6") (pinfunction "GPIO2/RTC_GPIO2/TOUCH2/ADC1_CH1_6") (pintype "passive"))
    )
    (net (code "26") (name "/GPIO3") (class "Default")
      (node (ref "J3") (pin "6") (pinfunction "6_6") (pintype "passive"))
      (node (ref "U3") (pin "7") (pinfunction "GPIO3/RTC_GPIO3/TOUCH3/ADC1_CH2_7") (pintype "passive"))
    )
    (net (code "27") (name "/GPIO4") (class "Default")
      (node (ref "J3") (pin "7") (pinfunction "7_7") (pintype "passive"))
      (node (ref "U3") (pin "8") (pinfunction "GPIO4/RTC_GPIO4/TOUCH4/ADC1_CH3_8") (pintype "passive"))
    )
    (net (code "28") (name "/GPIO5") (class "Default")
      (node (ref "J3") (pin "8") (pinfunction "8_8") (pintype "passive"))
      (node (ref "U3") (pin "9") (pinfunction "GPIO5/RTC_GPIO5/TOUCH5/ADC1_CH4_9") (pintype "passive"))
    )
    (net (code "29") (name "/GPIO6") (class "Default")
      (node (ref "J3") (pin "9") (pinfunction "9_9") (pintype "passive"))
      (node (ref "U3") (pin "10") (pinfunction "GPIO6/RTC_GPIO6/TOUCH6/ADC1_CH5_10") (pintype "passive"))
    )
    (net (code "30") (name "/GPIO7") (class "Default")
      (node (ref "J3") (pin "10") (pinfunction "10_10") (pintype "passive"))
      (node (ref "U3") (pin "11") (pinfunction "GPIO7/RTC_GPIO7/TOUCH7/ADC1_CH6_11") (pintype "passive"))
    )
    (net (code "31") (name "/GPIO8") (class "Default")
      (node (ref "J3") (pin "11") (pinfunction "11_11") (pintype "passive"))
      (node (ref "U3") (pin "12") (pinfunction "GPIO8/RTC_GPIO8/TOUCH8/ADC1_CH7/SUBSPICS1_12") (pintype "passive"))
    )
    (net (code "32") (name "/GPIO9") (class "Default")
      (node (ref "J3") (pin "12") (pinfunction "12_12") (pintype "passive"))
      (node (ref "U3") (pin "13") (pinfunction "GPIO9/RTC_GPIO9/TOUCH9/ADC1_CH8/FSPIHD/SUBSPIHD_13") (pintype "passive"))
    )
    (net (code "33") (name "/GPIO10") (class "Default")
      (node (ref "J3") (pin "13") (pinfunction "13_13") (pintype "passive"))
      (node (ref "U3") (pin "14") (pinfunction "GPIO10/RTC_GPIO10/TOUCH10/ADC1_CH9/FSPICS0/FSPIIO4/SUBSPICS0_14") (pintype "passive"))
    )
    (net (code "34") (name "/GPIO11") (class "Default")
      (node (ref "J3") (pin "14") (pinfunction "14_14") (pintype "passive"))
      (node (ref "U3") (pin "15") (pinfunction "GPIO11/RTC_GPIO11/TOUCH11/ADC2_CH0/FSPID/FSPIIO5/SUBSPID_15") (pintype "passive"))
    )
    (net (code "35") (name "/GPIO12") (class "Default")
      (node (ref "J3") (pin "15") (pinfunction "15_15") (pintype "passive"))
      (node (ref "U3") (pin "16") (pinfunction "GPIO12/RTC_GPIO12/TOUCH12/ADC2_CH1/FSPICLK/FSPIIO6/SUBSPICLK_16") (pintype "passive"))
    )
    (net (code "36") (name "/GPIO13") (class "Default")
      (node (ref "J3") (pin "16") (pinfunction "16_16") (pintype "passive"))
      (node (ref "U3") (pin "17") (pinfunction "GPIO13/RTC_GPIO13/TOUCH13/ADC2_CH2/FSPIQ/FSPIIO7/SUBSPIQ_17") (pintype "passive"))
    )
    (net (code "37") (name "/GPIO14") (class "Default")
      (node (ref "J3") (pin "17") (pinfunction "17_17") (pintype "passive"))
      (node (ref "U3") (pin "18") (pinfunction "GPIO14/RTC_GPIO14/TOUCH14/ADC2_CH3/FSPIWP/FSPIDQS/SUBSPIWP_18") (pintype "passive"))
    )
    (net (code "38") (name "/GPIO15") (class "Default")
      (node (ref "J3") (pin "18") (pinfunction "18_18") (pintype "passive"))
      (node (ref "U3") (pin "19") (pinfunction "GPIO15/RTC_GPIO15/U0RTS/ADC2_CH4/XTAL_32K_P_19") (pintype "passive"))
    )
    (net (code "39") (name "/GPIO16") (class "Default")
      (node (ref "J3") (pin "19") (pinfunction "19_19") (pintype "passive"))
      (node (ref "U3") (pin "20") (pinfunction "GPIO16/RTC_GPIO16/U0CTS/ADC2_CH5/XTAL_32K_N_20") (pintype "passive"))
    )
    (net (code "40") (name "/GPIO17") (class "Default")
      (node (ref "J3") (pin "20") (pinfunction "20_20") (pintype "passive"))
      (node (ref "U3") (pin "21") (pinfunction "GPIO17/RTC_GPIO17/U1TXD/ADC2_CH6_21") (pintype "passive"))
    )
    (net (code "41") (name "/GPIO18") (class "Default")
      (node (ref "J3") (pin "21") (pinfunction "21_21") (pintype "passive"))
      (node (ref "U3") (pin "22") (pinfunction "GPIO18/RTC_GPIO18/U1RXD/ADC2_CH7/CLK_OUT3_22") (pintype "passive"))
    )
    (net (code "42") (name "/GPIO21") (class "Default")
      (node (ref "J2") (pin "19") (pinfunction "19_19") (pintype "passive"))
      (node (ref "U3") (pin "25") (pinfunction "GPIO21/RTC_GPIO21_25") (pintype "passive"))
    )
    (net (code "43") (name "/GPIO26") (class "Default")
      (node (ref "J2") (pin "18") (pinfunction "18_18") (pintype "passive"))
      (node (ref "U3") (pin "26") (pinfunction "GPIO26/SPICS1_26") (pintype "passive"))
    )
    (net (code "44") (name "/GPIO33") (class "Default")
      (node (ref "J2") (pin "17") (pinfunction "17_17") (pintype "passive"))
      (node (ref "U3") (pin "28") (pinfunction "GPIO33/SPIIO4/FSPIHD/SUBSPIHD_28") (pintype "passive"))
    )
    (net (code "45") (name "/GPIO34") (class "Default")
      (node (ref "J2") (pin "16") (pinfunction "16_16") (pintype "passive"))
      (node (ref "U3") (pin "29") (pinfunction "GPIO34/SPIIO5/FSPICS0/SUBSPICS0_29") (pintype "passive"))
    )
    (net (code "46") (name "/GPIO35") (class "Default")
      (node (ref "J2") (pin "15") (pinfunction "15_15") (pintype "passive"))
      (node (ref "U3") (pin "31") (pinfunction "GPIO35/SPIIO6/FSPID/SUBSPID_31") (pintype "passive"))
    )
    (net (code "47") (name "/GPIO36") (class "Default")
      (node (ref "J2") (pin "14") (pinfunction "14_14") (pintype "passive"))
      (node (ref "U3") (pin "32") (pinfunction "GPIO36/SPIIO7/FSPICLK/SUBSPICLK_32") (pintype "passive"))
    )
    (net (code "48") (name "/GPIO37") (class "Default")
      (node (ref "J2") (pin "13") (pinfunction "13_13") (pintype "passive"))
      (node (ref "U3") (pin "33") (pinfunction "GPIO37/SPIDQS/FSPIQ/SUBSPIQ_33") (pintype "passive"))
    )
    (net (code "49") (name "/GPIO38") (class "Default")
      (node (ref "J2") (pin "12") (pinfunction "12_12") (pintype "passive"))
      (node (ref "U3") (pin "34") (pinfunction "GPIO38/FSPIWP/SUBSPIWP_34") (pintype "passive"))
    )
    (net (code "50") (name "/GPIO39") (class "Default")
      (node (ref "J2") (pin "11") (pinfunction "11_11") (pintype "passive"))
      (node (ref "U3") (pin "35") (pinfunction "MTCK/GPIO39/CLK_OUT3/SUBSPICS1_35") (pintype "passive"))
    )
    (net (code "51") (name "/GPIO40") (class "Default")
      (node (ref "J2") (pin "10") (pinfunction "10_10") (pintype "passive"))
      (node (ref "U3") (pin "36") (pinfunction "MTDO/GPIO40/CLK_OUT2_36") (pintype "passive"))
    )
    (net (code "52") (name "/GPIO41") (class "Default")
      (node (ref "J2") (pin "9") (pinfunction "9_9") (pintype "passive"))
      (node (ref "U3") (pin "37") (pinfunction "MTDI/GPIO41/CLK_OUT1_37") (pintype "passive"))
    )
    (net (code "53") (name "/GPIO42") (class "Default")
      (node (ref "J2") (pin "8") (pinfunction "8_8") (pintype "passive"))
      (node (ref "U3") (pin "38") (pinfunction "MTMS/GPIO42_38") (pintype "passive"))
    )
    (net (code "54") (name "/GPIO45") (class "Default")
      (node (ref "J2") (pin "5") (pinfunction "5_5") (pintype "passive"))
      (node (ref "U3") (pin "41") (pinfunction "GPIO45_41") (pintype "passive"))
    )
    (net (code "55") (name "/GPIO46") (class "Default")
      (node (ref "J2") (pin "4") (pinfunction "4_4") (pintype "passive"))
      (node (ref "U3") (pin "44") (pinfunction "GPIO46_44") (pintype "passive"))
    )
    (net (code "56") (name "/GPIO47") (class "Default")
      (node (ref "J2") (pin "23") (pinfunction "23_23") (pintype "passive"))
      (node (ref "U3") (pin "27") (pinfunction "GPIO47/SPICLK_P_DIFF/SUBSPICLK_P_DIFF_27") (pintype "passive"))
    )
    (net (code "57") (name "/GPIO48") (class "Default")
      (node (ref "J2") (pin "22") (pinfunction "22_22") (pintype "passive"))
      (node (ref "U3") (pin "30") (pinfunction "GPIO48/SPICLK_N_DIFF/SUBSPICLK_N_DIFF_30") (pintype "passive"))
    )
    (net (code "58") (name "/RTS_FTDI") (class "Default")
      (node (ref "Q1") (pin "2") (pinfunction "E_2") (pintype "passive"))
      (node (ref "R18") (pin "1") (pinfunction "1_1") (pintype "passive"))
      (node (ref "U1") (pin "19") (pinfunction "~{RTS}_19") (pintype "output"))
    )
    (net (code "59") (name "/RXD_FTDI") (class "Default")
      (node (ref "R19") (pin "2") (pinfunction "2_2") (pintype "passive"))
      (node (ref "U1") (pin "1") (pinfunction "RXD_1") (pintype "passive"))
    )
    (net (code "60") (name "/TXD_FTDI") (class "Default")
      (node (ref "R21") (pin "2") (pinfunction "2_2") (pintype "passive"))
      (node (ref "U1") (pin "17") (pinfunction "TXD_17") (pintype "output"))
    )
    (net (code "61") (name "/U0RXD") (class "Default")
      (node (ref "J2") (pin "6") (pinfunction "6_6") (pintype "passive"))
      (node (ref "R21") (pin "1") (pinfunction "1_1") (pintype "passive"))
      (node (ref "U3") (pin "40") (pinfunction "U0RXD/GPIO44/CLK_OUT2_40") (pintype "passive"))
    )
    (net (code "62") (name "/U0TXD") (class "Default")
      (node (ref "J2") (pin "7") (pinfunction "7_7") (pintype "passive"))
      (node (ref "R19") (pin "1") (pinfunction "1_1") (pintype "passive"))
      (node (ref "U3") (pin "39") (pinfunction "U0TXD/GPIO43/CLK_OUT1_39") (pintype "passive"))
    )
    (net (code "63") (name "/VBUS_SENSE") (class "Default")
      (node (ref "R10") (pin "1") (pinfunction "1_1") (pintype "passive"))
      (node (ref "R13") (pin "1") (pinfunction "1_1") (pintype "passive"))
      (node (ref "U1") (pin "16") (pinfunction "CBUS3_16") (pintype "bidirectional"))
    )
    (net (code "64") (name "GND") (class "Default")
      (node (ref "C1") (pin "1") (pinfunction "1_1") (pintype "passive"))
      (node (ref "C10") (pin "1") (pinfunction "1_1") (pintype "passive"))
      (node (ref "C11") (pin "1") (pinfunction "1_1") (pintype "passive"))
      (node (ref "C12") (pin "1") (pinfunction "1_1") (pintype "passive"))
      (node (ref "C13") (pin "1") (pinfunction "1_1") (pintype "passive"))
      (node (ref "C14") (pin "1") (pinfunction "1_1") (pintype "passive"))
      (node (ref "C15") (pin "1") (pinfunction "1_1") (pintype "passive"))
      (node (ref "C16") (pin "1") (pinfunction "1_1") (pintype "passive"))
      (node (ref "C17") (pin "1") (pinfunction "1_1") (pintype "passive"))
      (node (ref "C2") (pin "1") (pinfunction "1_1") (pintype "passive"))
      (node (ref "C3") (pin "1") (pinfunction "1_1") (pintype "passive"))
      (node (ref "C4") (pin "1") (pinfunction "1_1") (pintype "passive"))
      (node (ref "C5") (pin "1") (pinfunction "1_1") (pintype "passive"))
      (node (ref "C6") (pin "1") (pinfunction "1_1") (pintype "passive"))
      (node (ref "C7") (pin "1") (pinfunction "1_1") (pintype "passive"))
      (node (ref "C8") (pin "1") (pinfunction "1_1") (pintype "passive"))
      (node (ref "C9") (pin "1") (pinfunction "1_1") (pintype "passive"))
      (node (ref "D1") (pin "1") (pinfunction "K_1") (pintype "passive"))
      (node (ref "D3") (pin "1") (pinfunction "0_1") (pintype "passive"))
      (node (ref "D4") (pin "1") (pinfunction "0_1") (pintype "passive"))
      (node (ref "D5") (pin "1") (pinfunction "0_1") (pintype "passive"))
      (node (ref "D6") (pin "1") (pinfunction "0_1") (pintype "passive"))
      (node (ref "D7") (pin "1") (pinfunction "0_1") (pintype "passive"))
      (node (ref "D8") (pin "1") (pinfunction "0_1") (pintype "passive"))
      (node (ref "J1") (pin "A1B12") (pinfunction "GND_A1B12_A1B12") (pintype "passive"))
      (node (ref "J1") (pin "B1A12") (pinfunction "GND_B1A12_B1A12") (pintype "passive"))
      (node (ref "J1") (pin "S1") (pinfunction "SHIELD_1_S1") (pintype "passive"))
      (node (ref "J1") (pin "S2") (pinfunction "SHIELD_2_S2") (pintype "passive"))
      (node (ref "J1") (pin "S3") (pinfunction "SHIELD_3_S3") (pintype "passive"))
      (node (ref "J1") (pin "S4") (pinfunction "SHIELD_4_S4") (pintype "passive"))
      (node (ref "J2") (pin "2") (pinfunction "2_2") (pintype "passive"))
      (node (ref "J2") (pin "24") (pinfunction "24_24") (pintype "passive"))
      (node (ref "J3") (pin "1") (pinfunction "1_1") (pintype "passive"))
      (node (ref "J3") (pin "23") (pinfunction "23_23") (pintype "passive"))
      (node (ref "J4") (pin "A1B12") (pinfunction "GND_A1B12_A1B12") (pintype "passive"))
      (node (ref "J4") (pin "B1A12") (pinfunction "GND_B1A12_B1A12") (pintype "passive"))
      (node (ref "J4") (pin "S1") (pinfunction "SHIELD_1_S1") (pintype "passive"))
      (node (ref "J4") (pin "S2") (pinfunction "SHIELD_2_S2") (pintype "passive"))
      (node (ref "J4") (pin "S3") (pinfunction "SHIELD_3_S3") (pintype "passive"))
      (node (ref "J4") (pin "S4") (pinfunction "SHIELD_4_S4") (pintype "passive"))
      (node (ref "R11") (pin "1") (pinfunction "1_1") (pintype "passive"))
      (node (ref "R12") (pin "1") (pinfunction "1_1") (pintype "passive"))
      (node (ref "R13") (pin "2") (pinfunction "2_2") (pintype "passive"))
      (node (ref "R14") (pin "1") (pinfunction "1_1") (pintype "passive"))
      (node (ref "R15") (pin "1") (pinfunction "1_1") (pintype "passive"))
      (node (ref "R9") (pin "2") (pinfunction "2_2") (pintype "passive"))
      (node (ref "SW1") (pin "3") (pinfunction "3_3") (pintype "passive"))
      (node (ref "SW1") (pin "4") (pinfunction "4_4") (pintype "passive"))
      (node (ref "SW2") (pin "3") (pinfunction "3_3") (pintype "passive"))
      (node (ref "SW2") (pin "4") (pinfunction "4_4") (pintype "passive"))
      (node (ref "U1") (pin "13") (pinfunction "GND_13") (pintype "power_in"))
      (node (ref "U1") (pin "21") (pinfunction "GND_21") (pintype "power_in"))
      (node (ref "U1") (pin "3") (pinfunction "GND_3") (pintype "power_in"))
      (node (ref "U2") (pin "2") (pinfunction "46_2") (pintype "passive"))
      (node (ref "U2") (pin "4") (pinfunction "45_4") (pintype "passive"))
      (node (ref "U3") (pin "1") (pinfunction "GND_01_1") (pintype "passive"))
      (node (ref "U3") (pin "2") (pinfunction "GND_02_2") (pintype "passive"))
      (node (ref "U3") (pin "42") (pinfunction "GND_42") (pintype "passive"))
      (node (ref "U3") (pin "43") (pinfunction "GND_43") (pintype "passive"))
      (node (ref "U3") (pin "46") (pinfunction "GND_46_46") (pintype "passive"))
      (node (ref "U3") (pin "47") (pinfunction "GND_47_47") (pintype "passive"))
      (node (ref "U3") (pin "48") (pinfunction "GND_48_48") (pintype "passive"))
      (node (ref "U3") (pin "49") (pinfunction "GND_49_49") (pintype "passive"))
      (node (ref "U3") (pin "50") (pinfunction "GND_50_50") (pintype "passive"))
      (node (ref "U3") (pin "51") (pinfunction "GND_51_51") (pintype "passive"))
      (node (ref "U3") (pin "52") (pinfunction "GND_52_52") (pintype "passive"))
      (node (ref "U3") (pin "53") (pinfunction "GND_53_53") (pintype "passive"))
      (node (ref "U3") (pin "54") (pinfunction "GND_54_54") (pintype "passive"))
      (node (ref "U3") (pin "55") (pinfunction "GND_55_55") (pintype "passive"))
      (node (ref "U3") (pin "56") (pinfunction "GND_56_56") (pintype "passive"))
      (node (ref "U3") (pin "57") (pinfunction "GND_57_57") (pintype "passive"))
      (node (ref "U3") (pin "58") (pinfunction "GND_58_58") (pintype "passive"))
      (node (ref "U3") (pin "59") (pinfunction "GND_59_59") (pintype "passive"))
      (node (ref "U3") (pin "60") (pinfunction "GND_60_60") (pintype "passive"))
      (node (ref "U3") (pin "61") (pinfunction "GND_61_61") (pintype "passive"))
      (node (ref "U3") (pin "62") (pinfunction "GND_62_62") (pintype "passive"))
      (node (ref "U3") (pin "63") (pinfunction "GND_63_63") (pintype "passive"))
      (node (ref "U3") (pin "64") (pinfunction "GND_64_64") (pintype "passive"))
      (node (ref "U3") (pin "65") (pinfunction "GND_65_65") (pintype "passive"))
      (node (ref "U3") (pin "66") (pinfunction "GND_66_66") (pintype "passive"))
      (node (ref "U3") (pin "67") (pinfunction "GND_67_67") (pintype "passive"))
      (node (ref "U3") (pin "68") (pinfunction "GND_68_68") (pintype "passive"))
      (node (ref "U3") (pin "69") (pinfunction "GND_69_69") (pintype "passive"))
      (node (ref "U3") (pin "70") (pinfunction "GND_70_70") (pintype "passive"))
      (node (ref "U3") (pin "71") (pinfunction "GND_71_71") (pintype "passive"))
      (node (ref "U3") (pin "72") (pinfunction "GND_72_72") (pintype "passive"))
      (node (ref "U3") (pin "73") (pinfunction "GND_73_73") (pintype "passive"))
    )
    (net (code "65") (name "Net-(D1-A)") (class "Default")
      (node (ref "D1") (pin "2") (pinfunction "A_2") (pintype "passive"))
      (node (ref "R3") (pin "1") (pinfunction "1_1") (pintype "passive"))
    )
    (net (code "66") (name "Net-(D2-A)") (class "Default")
      (node (ref "D2") (pin "2") (pinfunction "A_2") (pintype "passive"))
      (node (ref "R4") (pin "1") (pinfunction "1_1") (pintype "passive"))
    )
    (net (code "67") (name "Net-(J1-CC1)") (class "Default")
      (node (ref "J1") (pin "A5") (pinfunction "CC1_A5") (pintype "passive"))
      (node (ref "R12") (pin "2") (pinfunction "2_2") (pintype "passive"))
    )
    (net (code "68") (name "Net-(J1-CC2)") (class "Default")
      (node (ref "J1") (pin "B5") (pinfunction "CC2_B5") (pintype "passive"))
      (node (ref "R11") (pin "2") (pinfunction "2_2") (pintype "passive"))
    )
    (net (code "69") (name "Net-(J4-CC1)") (class "Default")
      (node (ref "J4") (pin "A5") (pinfunction "CC1_A5") (pintype "passive"))
      (node (ref "R15") (pin "2") (pinfunction "2_2") (pintype "passive"))
    )
    (net (code "70") (name "Net-(J4-CC2)") (class "Default")
      (node (ref "J4") (pin "B5") (pinfunction "CC2_B5") (pintype "passive"))
      (node (ref "R14") (pin "2") (pinfunction "2_2") (pintype "passive"))
    )
    (net (code "71") (name "Net-(Q1-B)") (class "Default")
      (node (ref "Q1") (pin "1") (pinfunction "B_1") (pintype "passive"))
      (node (ref "R16") (pin "2") (pinfunction "2_2") (pintype "passive"))
    )
    (net (code "72") (name "Net-(Q2-B)") (class "Default")
      (node (ref "Q2") (pin "1") (pinfunction "B_1") (pintype "passive"))
      (node (ref "R18") (pin "2") (pinfunction "2_2") (pintype "passive"))
    )
    (net (code "73") (name "Net-(U1-CBUS0)") (class "Default")
      (node (ref "R9") (pin "1") (pinfunction "1_1") (pintype "passive"))
      (node (ref "U1") (pin "15") (pinfunction "CBUS0_15") (pintype "bidirectional"))
    )
    (net (code "74") (name "unconnected-(J1-SBU1-PadA8)") (class "Default")
      (node (ref "J1") (pin "A8") (pinfunction "SBU1_A8") (pintype "passive+no_connect"))
    )
    (net (code "75") (name "unconnected-(J1-SBU2-PadB8)") (class "Default")
      (node (ref "J1") (pin "B8") (pinfunction "SBU2_B8") (pintype "passive+no_connect"))
    )
    (net (code "76") (name "unconnected-(J3-Pad24)") (class "Default")
      (node (ref "J3") (pin "24") (pinfunction "24_24") (pintype "passive+no_connect"))
    )
    (net (code "77") (name "unconnected-(J4-SBU1-PadA8)") (class "Default")
      (node (ref "J4") (pin "A8") (pinfunction "SBU1_A8") (pintype "passive+no_connect"))
    )
    (net (code "78") (name "unconnected-(J4-SBU2-PadB8)") (class "Default")
      (node (ref "J4") (pin "B8") (pinfunction "SBU2_B8") (pintype "passive+no_connect"))
    )
    (net (code "79") (name "unconnected-(U1-CBUS1-Pad14)") (class "Default")
      (node (ref "U1") (pin "14") (pinfunction "CBUS1_14") (pintype "bidirectional+no_connect"))
    )
    (net (code "80") (name "unconnected-(U1-CBUS2-Pad7)") (class "Default")
      (node (ref "U1") (pin "7") (pinfunction "CBUS2_7") (pintype "bidirectional+no_connect"))
    )
    (net (code "81") (name "unconnected-(U1-~{CTS}-Pad6)") (class "Default")
      (node (ref "U1") (pin "6") (pinfunction "~{CTS}_6") (pintype "passive+no_connect"))
    )
    (net (code "82") (name "unconnected-(U1-~{DCD}-Pad5)") (class "Default")
      (node (ref "U1") (pin "5") (pinfunction "~{DCD}_5") (pintype "passive+no_connect"))
    )
    (net (code "83") (name "unconnected-(U1-~{DSR}-Pad4)") (class "Default")
      (node (ref "U1") (pin "4") (pinfunction "~{DSR}_4") (pintype "passive+no_connect"))
    )
    (net (code "84") (name "unconnected-(U1-~{RI}-Pad2)") (class "Default")
      (node (ref "U1") (pin "2") (pinfunction "~{RI}_2") (pintype "passive+no_connect"))
    )
  )
)
